# hd-gs.net
KiCad netlist of a schematic drawn in EAGLE
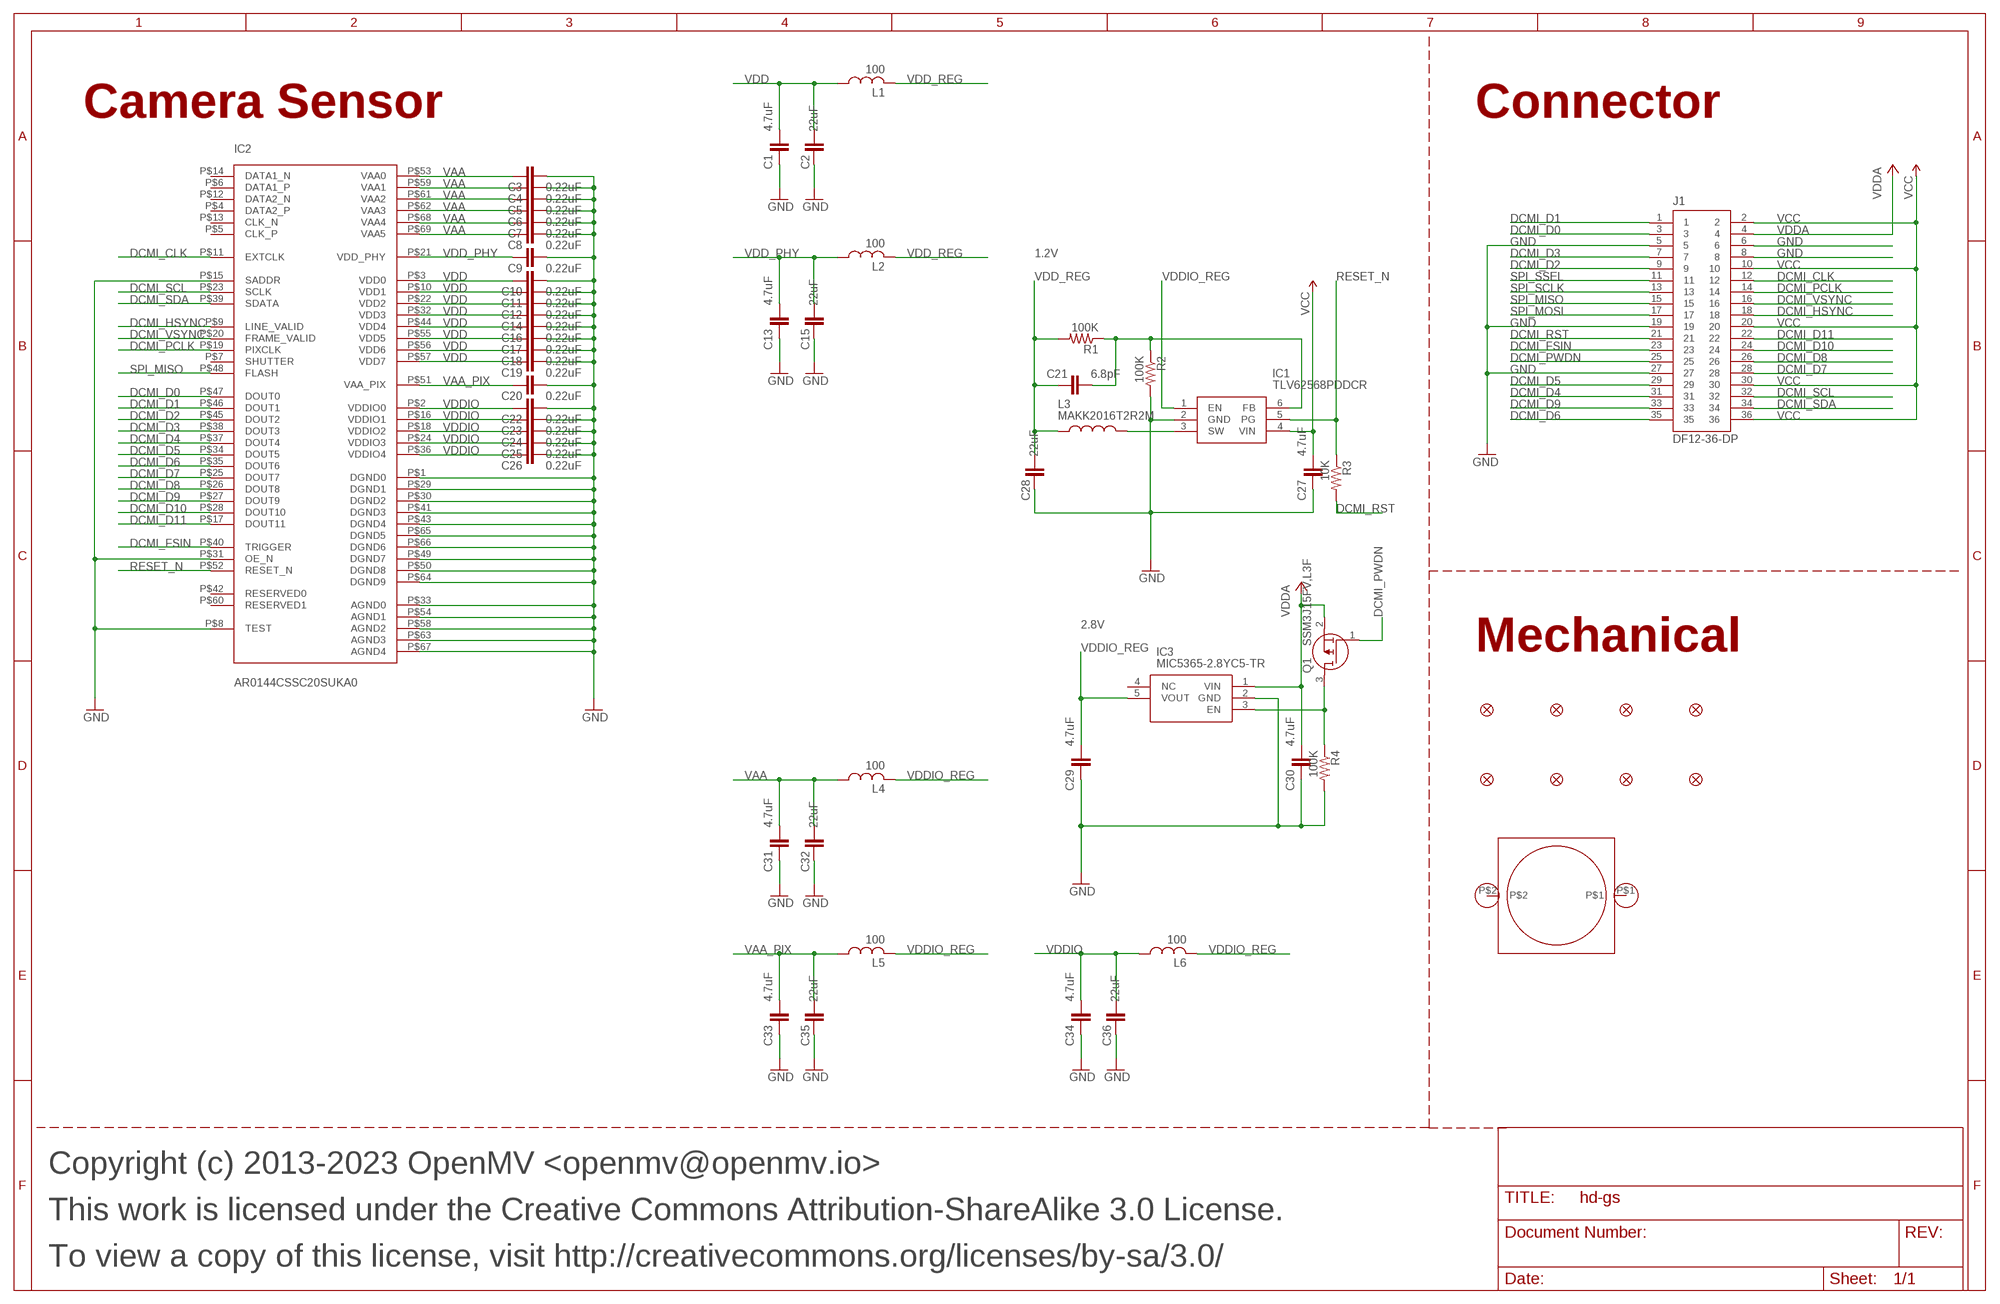
[diagram p0: schematic, sheet 1]

(export (version "E")
  (design (tool "Eeschema 10.0.6"))
  (components
    (comp (ref "C1")
      (value "4.7uF")
      (footprint "eagle-import:0402")
      (fields (field (name "MPN") "JMK105BBJ475MV-F"))
      (libsource (lib "eagle-import") (part "CAP_0402"))
    )
    (comp (ref "C2")
      (value "22uF")
      (footprint "eagle-import:0805")
      (fields (field (name "MPN") "CL21A226MQQNNNE"))
      (libsource (lib "eagle-import") (part "22UF-0805-6.3V-20%"))
    )
    (comp (ref "C3")
      (value "0.22uF")
      (footprint "eagle-import:C0201")
      (fields (field (name "MPN") "GRM033R60J224ME15D"))
      (libsource (lib "eagle-import") (part "C-EUC0201"))
    )
    (comp (ref "C4")
      (value "0.22uF")
      (footprint "eagle-import:C0201")
      (fields (field (name "MPN") "GRM033R60J224ME15D"))
      (libsource (lib "eagle-import") (part "C-EUC0201"))
    )
    (comp (ref "C5")
      (value "0.22uF")
      (footprint "eagle-import:C0201")
      (fields (field (name "MPN") "GRM033R60J224ME15D"))
      (libsource (lib "eagle-import") (part "C-EUC0201"))
    )
    (comp (ref "C6")
      (value "0.22uF")
      (footprint "eagle-import:C0201")
      (fields (field (name "MPN") "GRM033R60J224ME15D"))
      (libsource (lib "eagle-import") (part "C-EUC0201"))
    )
    (comp (ref "C7")
      (value "0.22uF")
      (footprint "eagle-import:C0201")
      (fields (field (name "MPN") "GRM033R60J224ME15D"))
      (libsource (lib "eagle-import") (part "C-EUC0201"))
    )
    (comp (ref "C8")
      (value "0.22uF")
      (footprint "eagle-import:C0201")
      (fields (field (name "MPN") "GRM033R60J224ME15D"))
      (libsource (lib "eagle-import") (part "C-EUC0201"))
    )
    (comp (ref "C9")
      (value "0.22uF")
      (footprint "eagle-import:C0201")
      (fields (field (name "MPN") "GRM033R60J224ME15D"))
      (libsource (lib "eagle-import") (part "C-EUC0201"))
    )
    (comp (ref "C10")
      (value "0.22uF")
      (footprint "eagle-import:C0201")
      (fields (field (name "MPN") "GRM033R60J224ME15D"))
      (libsource (lib "eagle-import") (part "C-EUC0201"))
    )
    (comp (ref "C11")
      (value "0.22uF")
      (footprint "eagle-import:C0201")
      (fields (field (name "MPN") "GRM033R60J224ME15D"))
      (libsource (lib "eagle-import") (part "C-EUC0201"))
    )
    (comp (ref "C12")
      (value "0.22uF")
      (footprint "eagle-import:C0201")
      (fields (field (name "MPN") "GRM033R60J224ME15D"))
      (libsource (lib "eagle-import") (part "C-EUC0201"))
    )
    (comp (ref "C13")
      (value "4.7uF")
      (footprint "eagle-import:0402")
      (fields (field (name "MPN") "JMK105BBJ475MV-F"))
      (libsource (lib "eagle-import") (part "CAP_0402"))
    )
    (comp (ref "C14")
      (value "0.22uF")
      (footprint "eagle-import:C0201")
      (fields (field (name "MPN") "GRM033R60J224ME15D"))
      (libsource (lib "eagle-import") (part "C-EUC0201"))
    )
    (comp (ref "C15")
      (value "22uF")
      (footprint "eagle-import:0805")
      (fields (field (name "MPN") "CL21A226MQQNNNE"))
      (libsource (lib "eagle-import") (part "22UF-0805-6.3V-20%"))
    )
    (comp (ref "C16")
      (value "0.22uF")
      (footprint "eagle-import:C0201")
      (fields (field (name "MPN") "GRM033R60J224ME15D"))
      (libsource (lib "eagle-import") (part "C-EUC0201"))
    )
    (comp (ref "C17")
      (value "0.22uF")
      (footprint "eagle-import:C0201")
      (fields (field (name "MPN") "GRM033R60J224ME15D"))
      (libsource (lib "eagle-import") (part "C-EUC0201"))
    )
    (comp (ref "C18")
      (value "0.22uF")
      (footprint "eagle-import:C0201")
      (fields (field (name "MPN") "GRM033R60J224ME15D"))
      (libsource (lib "eagle-import") (part "C-EUC0201"))
    )
    (comp (ref "C19")
      (value "0.22uF")
      (footprint "eagle-import:C0201")
      (fields (field (name "MPN") "GRM033R60J224ME15D"))
      (libsource (lib "eagle-import") (part "C-EUC0201"))
    )
    (comp (ref "C20")
      (value "0.22uF")
      (footprint "eagle-import:C0201")
      (fields (field (name "MPN") "GRM033R60J224ME15D"))
      (libsource (lib "eagle-import") (part "C-EUC0201"))
    )
    (comp (ref "C21")
      (value "6.8pF")
      (footprint "eagle-import:0402")
      (fields (field (name "MPN") "GRM1555C1H6R8DA01D"))
      (libsource (lib "eagle-import") (part "CAP_0402"))
    )
    (comp (ref "C22")
      (value "0.22uF")
      (footprint "eagle-import:C0201")
      (fields (field (name "MPN") "GRM033R60J224ME15D"))
      (libsource (lib "eagle-import") (part "C-EUC0201"))
    )
    (comp (ref "C23")
      (value "0.22uF")
      (footprint "eagle-import:C0201")
      (fields (field (name "MPN") "GRM033R60J224ME15D"))
      (libsource (lib "eagle-import") (part "C-EUC0201"))
    )
    (comp (ref "C24")
      (value "0.22uF")
      (footprint "eagle-import:C0201")
      (fields (field (name "MPN") "GRM033R60J224ME15D"))
      (libsource (lib "eagle-import") (part "C-EUC0201"))
    )
    (comp (ref "C25")
      (value "0.22uF")
      (footprint "eagle-import:C0201")
      (fields (field (name "MPN") "GRM033R60J224ME15D"))
      (libsource (lib "eagle-import") (part "C-EUC0201"))
    )
    (comp (ref "C26")
      (value "0.22uF")
      (footprint "eagle-import:C0201")
      (fields (field (name "MPN") "GRM033R60J224ME15D"))
      (libsource (lib "eagle-import") (part "C-EUC0201"))
    )
    (comp (ref "C27")
      (value "4.7uF")
      (footprint "eagle-import:0402")
      (fields (field (name "MPN") "JMK105BBJ475MV-F"))
      (libsource (lib "eagle-import") (part "CAP_0402"))
    )
    (comp (ref "C28")
      (value "22uF")
      (footprint "eagle-import:0805")
      (fields (field (name "MPN") "CL21A226MQQNNNE"))
      (libsource (lib "eagle-import") (part "22UF-0805-6.3V-20%"))
    )
    (comp (ref "C29")
      (value "4.7uF")
      (footprint "eagle-import:0402")
      (fields (field (name "MPN") "JMK105BBJ475MV-F"))
      (libsource (lib "eagle-import") (part "CAP_0402"))
    )
    (comp (ref "C30")
      (value "4.7uF")
      (footprint "eagle-import:0402")
      (fields (field (name "MPN") "JMK105BBJ475MV-F"))
      (libsource (lib "eagle-import") (part "CAP_0402"))
    )
    (comp (ref "C31")
      (value "4.7uF")
      (footprint "eagle-import:0402")
      (fields (field (name "MPN") "JMK105BBJ475MV-F"))
      (libsource (lib "eagle-import") (part "CAP_0402"))
    )
    (comp (ref "C32")
      (value "22uF")
      (footprint "eagle-import:0805")
      (fields (field (name "MPN") "CL21A226MQQNNNE"))
      (libsource (lib "eagle-import") (part "22UF-0805-6.3V-20%"))
    )
    (comp (ref "C33")
      (value "4.7uF")
      (footprint "eagle-import:0402")
      (fields (field (name "MPN") "JMK105BBJ475MV-F"))
      (libsource (lib "eagle-import") (part "CAP_0402"))
    )
    (comp (ref "C34")
      (value "4.7uF")
      (footprint "eagle-import:0402")
      (fields (field (name "MPN") "JMK105BBJ475MV-F"))
      (libsource (lib "eagle-import") (part "CAP_0402"))
    )
    (comp (ref "C35")
      (value "22uF")
      (footprint "eagle-import:0805")
      (fields (field (name "MPN") "CL21A226MQQNNNE"))
      (libsource (lib "eagle-import") (part "22UF-0805-6.3V-20%"))
    )
    (comp (ref "C36")
      (value "22uF")
      (footprint "eagle-import:0805")
      (fields (field (name "MPN") "CL21A226MQQNNNE"))
      (libsource (lib "eagle-import") (part "22UF-0805-6.3V-20%"))
    )
    (comp (ref "FD1")
      (value "FIDUCIAL1X2")
      (footprint "eagle-import:FIDUCIAL-1X2")
      (libsource (lib "eagle-import") (part "FIDUCIAL1X2"))
    )
    (comp (ref "FD2")
      (value "FIDUCIAL1X2")
      (footprint "eagle-import:FIDUCIAL-1X2")
      (libsource (lib "eagle-import") (part "FIDUCIAL1X2"))
    )
    (comp (ref "FD3")
      (value "FIDUCIAL1X2")
      (footprint "eagle-import:FIDUCIAL-1X2")
      (libsource (lib "eagle-import") (part "FIDUCIAL1X2"))
    )
    (comp (ref "FD4")
      (value "FIDUCIAL1X2")
      (footprint "eagle-import:FIDUCIAL-1X2")
      (libsource (lib "eagle-import") (part "FIDUCIAL1X2"))
    )
    (comp (ref "FD5")
      (value "FIDUCIAL1X2")
      (footprint "eagle-import:FIDUCIAL-1X2")
      (libsource (lib "eagle-import") (part "FIDUCIAL1X2"))
    )
    (comp (ref "FD6")
      (value "FIDUCIAL1X2")
      (footprint "eagle-import:FIDUCIAL-1X2")
      (libsource (lib "eagle-import") (part "FIDUCIAL1X2"))
    )
    (comp (ref "FD7")
      (value "FIDUCIAL1X2")
      (footprint "eagle-import:FIDUCIAL-1X2")
      (libsource (lib "eagle-import") (part "FIDUCIAL1X2"))
    )
    (comp (ref "FD8")
      (value "FIDUCIAL1X2")
      (footprint "eagle-import:FIDUCIAL-1X2")
      (libsource (lib "eagle-import") (part "FIDUCIAL1X2"))
    )
    (comp (ref "H1")
      (value "LENSMOUNT20MM")
      (footprint "eagle-import:LENSMOUNT-20MM")
      (libsource (lib "eagle-import") (part "LENSMOUNT20MM"))
    )
    (comp (ref "IC1")
      (value "TLV62568PDDCR")
      (footprint "eagle-import:SOT95P280X110-6N")
      (fields (field (name "MOUSER_PART_NUMBER") "595-TLV62568PDDCR"))
      (libsource (lib "eagle-import") (part "TLV62568PDDCR"))
    )
    (comp (ref "IC2")
      (value "AR0144CSSC20SUKA0")
      (footprint "eagle-import:AR0144CSSC20SUKA0")
      (fields (field (name "MPN") "AR0144CSSC20SUKA0-CRBR"))
      (libsource (lib "eagle-import") (part "AR0144CSSC20SUKA0"))
    )
    (comp (ref "IC3")
      (value "MIC5365-2.8YC5-TR")
      (footprint "eagle-import:SOT65P210X110-5N")
      (fields (field (name "MOUSER_PART_NUMBER") "998-MIC5365-2.8YC5TR"))
      (libsource (lib "eagle-import") (part "MIC5365-2.8YC5-TR"))
    )
    (comp (ref "J1")
      (value "DF12-36-DP")
      (footprint "eagle-import:DF12-36-DP")
      (fields (field (name "MPN") "DF12NB(3.0)-36DP-0.5V(51)"))
      (libsource (lib "eagle-import") (part "DF12-36-DP"))
    )
    (comp (ref "L1")
      (value "100")
      (footprint "eagle-import:0402")
      (fields (field (name "MPN") "MFBM1V1005-101-R"))
      (libsource (lib "eagle-import") (part "INDUCTOR_0402"))
    )
    (comp (ref "L2")
      (value "100")
      (footprint "eagle-import:0402")
      (fields (field (name "MPN") "MFBM1V1005-101-R"))
      (libsource (lib "eagle-import") (part "INDUCTOR_0402"))
    )
    (comp (ref "L3")
      (value "MAKK2016T2R2M")
      (footprint "eagle-import:INDC2016X100N")
      (fields (field (name "MF") "Taiyo Yuden"))
      (libsource (lib "eagle-import") (part "MAKK2016T2R2M"))
    )
    (comp (ref "L4")
      (value "100")
      (footprint "eagle-import:0402")
      (fields (field (name "MPN") "MFBM1V1005-101-R"))
      (libsource (lib "eagle-import") (part "INDUCTOR_0402"))
    )
    (comp (ref "L5")
      (value "100")
      (footprint "eagle-import:0402")
      (fields (field (name "MPN") "MFBM1V1005-101-R"))
      (libsource (lib "eagle-import") (part "INDUCTOR_0402"))
    )
    (comp (ref "L6")
      (value "100")
      (footprint "eagle-import:0402")
      (fields (field (name "MPN") "MFBM1V1005-101-R"))
      (libsource (lib "eagle-import") (part "INDUCTOR_0402"))
    )
    (comp (ref "Q1")
      (value "SSM3J15FV,L3F")
      (footprint "eagle-import:SSM3J15FVL3F")
      (fields (field (name "MOUSER_PART_NUMBER") "757-SSM3J15FVL3F"))
      (libsource (lib "eagle-import") (part "SSM3J15FV,L3F"))
    )
    (comp (ref "R1")
      (value "100K")
      (footprint "eagle-import:R0402")
      (fields (field (name "MPN") "AC0402FR-07100KL"))
      (libsource (lib "eagle-import") (part "R-US_R0402"))
    )
    (comp (ref "R2")
      (value "100K")
      (footprint "eagle-import:R0402")
      (fields (field (name "MPN") "AC0402FR-07100KL"))
      (libsource (lib "eagle-import") (part "R-US_R0402"))
    )
    (comp (ref "R3")
      (value "10K")
      (footprint "eagle-import:R0402")
      (fields (field (name "MPN") "AC0402FR-1310KL"))
      (libsource (lib "eagle-import") (part "R-US_R0402"))
    )
    (comp (ref "R4")
      (value "100K")
      (footprint "eagle-import:R0402")
      (fields (field (name "MPN") "AC0402FR-07100KL"))
      (libsource (lib "eagle-import") (part "R-US_R0402"))
    )
  )
  (nets
    (net (code "1") (name "/DCMI_CLK") (class "Default")
      (node (ref "IC2") (pin "P$11") (pinfunction "EXTCLK_P$11") (pintype "input"))
      (node (ref "J1") (pin "12") (pinfunction "12_12") (pintype "bidirectional"))
    )
    (net (code "2") (name "/DCMI_D0") (class "Default")
      (node (ref "IC2") (pin "P$47") (pinfunction "DOUT0_P$47") (pintype "output"))
      (node (ref "J1") (pin "3") (pinfunction "3_3") (pintype "bidirectional"))
    )
    (net (code "3") (name "/DCMI_D1") (class "Default")
      (node (ref "IC2") (pin "P$46") (pinfunction "DOUT1_P$46") (pintype "output"))
      (node (ref "J1") (pin "1") (pinfunction "1_1") (pintype "bidirectional"))
    )
    (net (code "4") (name "/DCMI_D2") (class "Default")
      (node (ref "IC2") (pin "P$45") (pinfunction "DOUT2_P$45") (pintype "output"))
      (node (ref "J1") (pin "9") (pinfunction "9_9") (pintype "bidirectional"))
    )
    (net (code "5") (name "/DCMI_D3") (class "Default")
      (node (ref "IC2") (pin "P$38") (pinfunction "DOUT3_P$38") (pintype "output"))
      (node (ref "J1") (pin "7") (pinfunction "7_7") (pintype "bidirectional"))
    )
    (net (code "6") (name "/DCMI_D4") (class "Default")
      (node (ref "IC2") (pin "P$37") (pinfunction "DOUT4_P$37") (pintype "output"))
      (node (ref "J1") (pin "31") (pinfunction "31_31") (pintype "bidirectional"))
    )
    (net (code "7") (name "/DCMI_D5") (class "Default")
      (node (ref "IC2") (pin "P$34") (pinfunction "DOUT5_P$34") (pintype "output"))
      (node (ref "J1") (pin "29") (pinfunction "29_29") (pintype "bidirectional"))
    )
    (net (code "8") (name "/DCMI_D6") (class "Default")
      (node (ref "IC2") (pin "P$35") (pinfunction "DOUT6_P$35") (pintype "output"))
      (node (ref "J1") (pin "35") (pinfunction "35_35") (pintype "bidirectional"))
    )
    (net (code "9") (name "/DCMI_D7") (class "Default")
      (node (ref "IC2") (pin "P$25") (pinfunction "DOUT7_P$25") (pintype "output"))
      (node (ref "J1") (pin "28") (pinfunction "28_28") (pintype "bidirectional"))
    )
    (net (code "10") (name "/DCMI_D8") (class "Default")
      (node (ref "IC2") (pin "P$26") (pinfunction "DOUT8_P$26") (pintype "output"))
      (node (ref "J1") (pin "26") (pinfunction "26_26") (pintype "bidirectional"))
    )
    (net (code "11") (name "/DCMI_D9") (class "Default")
      (node (ref "IC2") (pin "P$27") (pinfunction "DOUT9_P$27") (pintype "output"))
      (node (ref "J1") (pin "33") (pinfunction "33_33") (pintype "bidirectional"))
    )
    (net (code "12") (name "/DCMI_D10") (class "Default")
      (node (ref "IC2") (pin "P$28") (pinfunction "DOUT10_P$28") (pintype "output"))
      (node (ref "J1") (pin "24") (pinfunction "24_24") (pintype "bidirectional"))
    )
    (net (code "13") (name "/DCMI_D11") (class "Default")
      (node (ref "IC2") (pin "P$17") (pinfunction "DOUT11_P$17") (pintype "output"))
      (node (ref "J1") (pin "22") (pinfunction "22_22") (pintype "bidirectional"))
    )
    (net (code "14") (name "/DCMI_FSIN") (class "Default")
      (node (ref "IC2") (pin "P$40") (pinfunction "TRIGGER_P$40") (pintype "input"))
      (node (ref "J1") (pin "23") (pinfunction "23_23") (pintype "bidirectional"))
    )
    (net (code "15") (name "/DCMI_HSYNC") (class "Default")
      (node (ref "IC2") (pin "P$9") (pinfunction "LINE_VALID_P$9") (pintype "output"))
      (node (ref "J1") (pin "18") (pinfunction "18_18") (pintype "bidirectional"))
    )
    (net (code "16") (name "/DCMI_PCLK") (class "Default")
      (node (ref "IC2") (pin "P$19") (pinfunction "PIXCLK_P$19") (pintype "output"))
      (node (ref "J1") (pin "14") (pinfunction "14_14") (pintype "bidirectional"))
    )
    (net (code "17") (name "/DCMI_PWDN") (class "Default")
      (node (ref "J1") (pin "25") (pinfunction "25_25") (pintype "bidirectional"))
      (node (ref "Q1") (pin "1") (pinfunction "G_1") (pintype "bidirectional"))
    )
    (net (code "18") (name "/DCMI_RST") (class "Default")
      (node (ref "J1") (pin "21") (pinfunction "21_21") (pintype "bidirectional"))
      (node (ref "R3") (pin "2") (pinfunction "2_2") (pintype "passive"))
    )
    (net (code "19") (name "/DCMI_SCL") (class "Default")
      (node (ref "IC2") (pin "P$23") (pinfunction "SCLK_P$23") (pintype "input"))
      (node (ref "J1") (pin "32") (pinfunction "32_32") (pintype "bidirectional"))
    )
    (net (code "20") (name "/DCMI_SDA") (class "Default")
      (node (ref "IC2") (pin "P$39") (pinfunction "SDATA_P$39") (pintype "bidirectional"))
      (node (ref "J1") (pin "34") (pinfunction "34_34") (pintype "bidirectional"))
    )
    (net (code "21") (name "/DCMI_VSYNC") (class "Default")
      (node (ref "IC2") (pin "P$20") (pinfunction "FRAME_VALID_P$20") (pintype "output"))
      (node (ref "J1") (pin "16") (pinfunction "16_16") (pintype "bidirectional"))
    )
    (net (code "22") (name "/P$1") (class "Default")
      (node (ref "H1") (pin "P$1") (pinfunction "P$1_P$1") (pintype "power_in"))
    )
    (net (code "23") (name "/P$2") (class "Default")
      (node (ref "H1") (pin "P$2") (pinfunction "P$2_P$2") (pintype "power_in"))
    )
    (net (code "24") (name "/RESET_N") (class "Default")
      (node (ref "IC1") (pin "5") (pinfunction "PG_5") (pintype "bidirectional"))
      (node (ref "IC2") (pin "P$52") (pinfunction "RESET_N_P$52") (pintype "input"))
      (node (ref "R3") (pin "1") (pinfunction "1_1") (pintype "passive"))
    )
    (net (code "25") (name "/SPI_MISO") (class "Default")
      (node (ref "IC2") (pin "P$48") (pinfunction "FLASH_P$48") (pintype "output"))
      (node (ref "J1") (pin "15") (pinfunction "15_15") (pintype "bidirectional"))
    )
    (net (code "26") (name "/SPI_MOSI") (class "Default")
      (node (ref "J1") (pin "17") (pinfunction "17_17") (pintype "bidirectional"))
    )
    (net (code "27") (name "/SPI_SCLK") (class "Default")
      (node (ref "J1") (pin "13") (pinfunction "13_13") (pintype "bidirectional"))
    )
    (net (code "28") (name "/SPI_SSEL") (class "Default")
      (node (ref "J1") (pin "11") (pinfunction "11_11") (pintype "bidirectional"))
    )
    (net (code "29") (name "/VAA") (class "Default")
      (node (ref "C3") (pin "1") (pinfunction "1_1") (pintype "passive"))
      (node (ref "C31") (pin "2") (pinfunction "2_2") (pintype "passive"))
      (node (ref "C32") (pin "2") (pinfunction "2_2") (pintype "passive"))
      (node (ref "C4") (pin "1") (pinfunction "1_1") (pintype "passive"))
      (node (ref "C5") (pin "1") (pinfunction "1_1") (pintype "passive"))
      (node (ref "C6") (pin "1") (pinfunction "1_1") (pintype "passive"))
      (node (ref "C7") (pin "1") (pinfunction "1_1") (pintype "passive"))
      (node (ref "C8") (pin "1") (pinfunction "1_1") (pintype "passive"))
      (node (ref "IC2") (pin "P$53") (pinfunction "VAA0_P$53") (pintype "power_in"))
      (node (ref "IC2") (pin "P$59") (pinfunction "VAA1_P$59") (pintype "power_in"))
      (node (ref "IC2") (pin "P$61") (pinfunction "VAA2_P$61") (pintype "power_in"))
      (node (ref "IC2") (pin "P$62") (pinfunction "VAA3_P$62") (pintype "power_in"))
      (node (ref "IC2") (pin "P$68") (pinfunction "VAA4_P$68") (pintype "power_in"))
      (node (ref "IC2") (pin "P$69") (pinfunction "VAA5_P$69") (pintype "power_in"))
      (node (ref "L4") (pin "1") (pinfunction "P$1_1") (pintype "passive"))
    )
    (net (code "30") (name "/VAA_PIX") (class "Default")
      (node (ref "C20") (pin "1") (pinfunction "1_1") (pintype "passive"))
      (node (ref "C33") (pin "2") (pinfunction "2_2") (pintype "passive"))
      (node (ref "C35") (pin "2") (pinfunction "2_2") (pintype "passive"))
      (node (ref "IC2") (pin "P$51") (pinfunction "VAA_PIX_P$51") (pintype "power_in"))
      (node (ref "L5") (pin "1") (pinfunction "P$1_1") (pintype "passive"))
    )
    (net (code "31") (name "/VDD") (class "Default")
      (node (ref "C1") (pin "2") (pinfunction "2_2") (pintype "passive"))
      (node (ref "C10") (pin "1") (pinfunction "1_1") (pintype "passive"))
      (node (ref "C11") (pin "1") (pinfunction "1_1") (pintype "passive"))
      (node (ref "C12") (pin "1") (pinfunction "1_1") (pintype "passive"))
      (node (ref "C14") (pin "1") (pinfunction "1_1") (pintype "passive"))
      (node (ref "C16") (pin "1") (pinfunction "1_1") (pintype "passive"))
      (node (ref "C17") (pin "1") (pinfunction "1_1") (pintype "passive"))
      (node (ref "C18") (pin "1") (pinfunction "1_1") (pintype "passive"))
      (node (ref "C19") (pin "1") (pinfunction "1_1") (pintype "passive"))
      (node (ref "C2") (pin "2") (pinfunction "2_2") (pintype "passive"))
      (node (ref "IC2") (pin "P$10") (pinfunction "VDD1_P$10") (pintype "power_in"))
      (node (ref "IC2") (pin "P$22") (pinfunction "VDD2_P$22") (pintype "power_in"))
      (node (ref "IC2") (pin "P$3") (pinfunction "VDD0_P$3") (pintype "power_in"))
      (node (ref "IC2") (pin "P$32") (pinfunction "VDD3_P$32") (pintype "power_in"))
      (node (ref "IC2") (pin "P$44") (pinfunction "VDD4_P$44") (pintype "power_in"))
      (node (ref "IC2") (pin "P$55") (pinfunction "VDD5_P$55") (pintype "power_in"))
      (node (ref "IC2") (pin "P$56") (pinfunction "VDD6_P$56") (pintype "power_in"))
      (node (ref "IC2") (pin "P$57") (pinfunction "VDD7_P$57") (pintype "power_in"))
      (node (ref "L1") (pin "1") (pinfunction "P$1_1") (pintype "passive"))
    )
    (net (code "32") (name "/VDDIO") (class "Default")
      (node (ref "C22") (pin "1") (pinfunction "1_1") (pintype "passive"))
      (node (ref "C23") (pin "1") (pinfunction "1_1") (pintype "passive"))
      (node (ref "C24") (pin "1") (pinfunction "1_1") (pintype "passive"))
      (node (ref "C25") (pin "1") (pinfunction "1_1") (pintype "passive"))
      (node (ref "C26") (pin "1") (pinfunction "1_1") (pintype "passive"))
      (node (ref "C34") (pin "2") (pinfunction "2_2") (pintype "passive"))
      (node (ref "C36") (pin "2") (pinfunction "2_2") (pintype "passive"))
      (node (ref "IC2") (pin "P$16") (pinfunction "VDDIO1_P$16") (pintype "power_in"))
      (node (ref "IC2") (pin "P$18") (pinfunction "VDDIO2_P$18") (pintype "power_in"))
      (node (ref "IC2") (pin "P$2") (pinfunction "VDDIO0_P$2") (pintype "power_in"))
      (node (ref "IC2") (pin "P$24") (pinfunction "VDDIO3_P$24") (pintype "power_in"))
      (node (ref "IC2") (pin "P$36") (pinfunction "VDDIO4_P$36") (pintype "power_in"))
      (node (ref "L6") (pin "1") (pinfunction "P$1_1") (pintype "passive"))
    )
    (net (code "33") (name "/VDDIO_REG") (class "Default")
      (node (ref "C29") (pin "2") (pinfunction "2_2") (pintype "passive"))
      (node (ref "IC1") (pin "1") (pinfunction "EN_1") (pintype "bidirectional"))
      (node (ref "IC3") (pin "5") (pinfunction "VOUT_5") (pintype "bidirectional"))
      (node (ref "L4") (pin "2") (pinfunction "P$2_2") (pintype "passive"))
      (node (ref "L5") (pin "2") (pinfunction "P$2_2") (pintype "passive"))
      (node (ref "L6") (pin "2") (pinfunction "P$2_2") (pintype "passive"))
    )
    (net (code "34") (name "/VDD_PHY") (class "Default")
      (node (ref "C13") (pin "2") (pinfunction "2_2") (pintype "passive"))
      (node (ref "C15") (pin "2") (pinfunction "2_2") (pintype "passive"))
      (node (ref "C9") (pin "1") (pinfunction "1_1") (pintype "passive"))
      (node (ref "IC2") (pin "P$21") (pinfunction "VDD_PHY_P$21") (pintype "power_in"))
      (node (ref "L2") (pin "1") (pinfunction "P$1_1") (pintype "passive"))
    )
    (net (code "35") (name "/VDD_REG") (class "Default")
      (node (ref "C21") (pin "1") (pinfunction "1_1") (pintype "passive"))
      (node (ref "C28") (pin "2") (pinfunction "2_2") (pintype "passive"))
      (node (ref "L1") (pin "2") (pinfunction "P$2_2") (pintype "passive"))
      (node (ref "L2") (pin "2") (pinfunction "P$2_2") (pintype "passive"))
      (node (ref "L3") (pin "1") (pinfunction "1_1") (pintype "passive"))
      (node (ref "R1") (pin "2") (pinfunction "2_2") (pintype "passive"))
    )
    (net (code "36") (name "GND") (class "Default")
      (node (ref "C1") (pin "1") (pinfunction "1_1") (pintype "passive"))
      (node (ref "C10") (pin "2") (pinfunction "2_2") (pintype "passive"))
      (node (ref "C11") (pin "2") (pinfunction "2_2") (pintype "passive"))
      (node (ref "C12") (pin "2") (pinfunction "2_2") (pintype "passive"))
      (node (ref "C13") (pin "1") (pinfunction "1_1") (pintype "passive"))
      (node (ref "C14") (pin "2") (pinfunction "2_2") (pintype "passive"))
      (node (ref "C15") (pin "1") (pinfunction "1_1") (pintype "passive"))
      (node (ref "C16") (pin "2") (pinfunction "2_2") (pintype "passive"))
      (node (ref "C17") (pin "2") (pinfunction "2_2") (pintype "passive"))
      (node (ref "C18") (pin "2") (pinfunction "2_2") (pintype "passive"))
      (node (ref "C19") (pin "2") (pinfunction "2_2") (pintype "passive"))
      (node (ref "C2") (pin "1") (pinfunction "1_1") (pintype "passive"))
      (node (ref "C20") (pin "2") (pinfunction "2_2") (pintype "passive"))
      (node (ref "C22") (pin "2") (pinfunction "2_2") (pintype "passive"))
      (node (ref "C23") (pin "2") (pinfunction "2_2") (pintype "passive"))
      (node (ref "C24") (pin "2") (pinfunction "2_2") (pintype "passive"))
      (node (ref "C25") (pin "2") (pinfunction "2_2") (pintype "passive"))
      (node (ref "C26") (pin "2") (pinfunction "2_2") (pintype "passive"))
      (node (ref "C27") (pin "1") (pinfunction "1_1") (pintype "passive"))
      (node (ref "C28") (pin "1") (pinfunction "1_1") (pintype "passive"))
      (node (ref "C29") (pin "1") (pinfunction "1_1") (pintype "passive"))
      (node (ref "C3") (pin "2") (pinfunction "2_2") (pintype "passive"))
      (node (ref "C30") (pin "1") (pinfunction "1_1") (pintype "passive"))
      (node (ref "C31") (pin "1") (pinfunction "1_1") (pintype "passive"))
      (node (ref "C32") (pin "1") (pinfunction "1_1") (pintype "passive"))
      (node (ref "C33") (pin "1") (pinfunction "1_1") (pintype "passive"))
      (node (ref "C34") (pin "1") (pinfunction "1_1") (pintype "passive"))
      (node (ref "C35") (pin "1") (pinfunction "1_1") (pintype "passive"))
      (node (ref "C36") (pin "1") (pinfunction "1_1") (pintype "passive"))
      (node (ref "C4") (pin "2") (pinfunction "2_2") (pintype "passive"))
      (node (ref "C5") (pin "2") (pinfunction "2_2") (pintype "passive"))
      (node (ref "C6") (pin "2") (pinfunction "2_2") (pintype "passive"))
      (node (ref "C7") (pin "2") (pinfunction "2_2") (pintype "passive"))
      (node (ref "C8") (pin "2") (pinfunction "2_2") (pintype "passive"))
      (node (ref "C9") (pin "2") (pinfunction "2_2") (pintype "passive"))
      (node (ref "IC1") (pin "2") (pinfunction "GND_2") (pintype "bidirectional"))
      (node (ref "IC2") (pin "P$1") (pinfunction "DGND0_P$1") (pintype "power_in"))
      (node (ref "IC2") (pin "P$15") (pinfunction "SADDR_P$15") (pintype "input"))
      (node (ref "IC2") (pin "P$29") (pinfunction "DGND1_P$29") (pintype "power_in"))
      (node (ref "IC2") (pin "P$30") (pinfunction "DGND2_P$30") (pintype "power_in"))
      (node (ref "IC2") (pin "P$31") (pinfunction "OE_N_P$31") (pintype "input"))
      (node (ref "IC2") (pin "P$33") (pinfunction "AGND0_P$33") (pintype "power_in"))
      (node (ref "IC2") (pin "P$41") (pinfunction "DGND3_P$41") (pintype "power_in"))
      (node (ref "IC2") (pin "P$43") (pinfunction "DGND4_P$43") (pintype "power_in"))
      (node (ref "IC2") (pin "P$49") (pinfunction "DGND7_P$49") (pintype "power_in"))
      (node (ref "IC2") (pin "P$50") (pinfunction "DGND8_P$50") (pintype "power_in"))
      (node (ref "IC2") (pin "P$54") (pinfunction "AGND1_P$54") (pintype "power_in"))
      (node (ref "IC2") (pin "P$58") (pinfunction "AGND2_P$58") (pintype "power_in"))
      (node (ref "IC2") (pin "P$63") (pinfunction "AGND3_P$63") (pintype "power_in"))
      (node (ref "IC2") (pin "P$64") (pinfunction "DGND9_P$64") (pintype "power_in"))
      (node (ref "IC2") (pin "P$65") (pinfunction "DGND5_P$65") (pintype "power_in"))
      (node (ref "IC2") (pin "P$66") (pinfunction "DGND6_P$66") (pintype "power_in"))
      (node (ref "IC2") (pin "P$67") (pinfunction "AGND4_P$67") (pintype "power_in"))
      (node (ref "IC2") (pin "P$8") (pinfunction "TEST_P$8") (pintype "input"))
      (node (ref "IC3") (pin "2") (pinfunction "GND_2") (pintype "bidirectional"))
      (node (ref "J1") (pin "19") (pinfunction "19_19") (pintype "bidirectional"))
      (node (ref "J1") (pin "27") (pinfunction "27_27") (pintype "bidirectional"))
      (node (ref "J1") (pin "5") (pinfunction "5_5") (pintype "bidirectional"))
      (node (ref "J1") (pin "6") (pinfunction "6_6") (pintype "bidirectional"))
      (node (ref "J1") (pin "8") (pinfunction "8_8") (pintype "bidirectional"))
      (node (ref "R2") (pin "2") (pinfunction "2_2") (pintype "passive"))
      (node (ref "R4") (pin "2") (pinfunction "2_2") (pintype "passive"))
    )
    (net (code "37") (name "Net-(IC1-FB)") (class "Default")
      (node (ref "C21") (pin "2") (pinfunction "2_2") (pintype "passive"))
      (node (ref "IC1") (pin "6") (pinfunction "FB_6") (pintype "bidirectional"))
      (node (ref "R1") (pin "1") (pinfunction "1_1") (pintype "passive"))
      (node (ref "R2") (pin "1") (pinfunction "1_1") (pintype "passive"))
    )
    (net (code "38") (name "Net-(IC1-SW)") (class "Default")
      (node (ref "IC1") (pin "3") (pinfunction "SW_3") (pintype "bidirectional"))
      (node (ref "L3") (pin "2") (pinfunction "2_2") (pintype "passive"))
    )
    (net (code "39") (name "Net-(IC3-EN)") (class "Default")
      (node (ref "IC3") (pin "3") (pinfunction "EN_3") (pintype "bidirectional"))
      (node (ref "Q1") (pin "3") (pinfunction "D_3") (pintype "bidirectional"))
      (node (ref "R4") (pin "1") (pinfunction "1_1") (pintype "passive"))
    )
    (net (code "40") (name "VCC") (class "Default")
      (node (ref "C27") (pin "2") (pinfunction "2_2") (pintype "passive"))
      (node (ref "IC1") (pin "4") (pinfunction "VIN_4") (pintype "bidirectional"))
      (node (ref "J1") (pin "10") (pinfunction "10_10") (pintype "bidirectional"))
      (node (ref "J1") (pin "2") (pinfunction "2_2") (pintype "bidirectional"))
      (node (ref "J1") (pin "20") (pinfunction "20_20") (pintype "bidirectional"))
      (node (ref "J1") (pin "30") (pinfunction "30_30") (pintype "bidirectional"))
      (node (ref "J1") (pin "36") (pinfunction "36_36") (pintype "bidirectional"))
    )
    (net (code "41") (name "VDDA") (class "Default")
      (node (ref "C30") (pin "2") (pinfunction "2_2") (pintype "passive"))
      (node (ref "IC3") (pin "1") (pinfunction "VIN_1") (pintype "bidirectional"))
      (node (ref "J1") (pin "4") (pinfunction "4_4") (pintype "bidirectional"))
      (node (ref "Q1") (pin "2") (pinfunction "S_2") (pintype "bidirectional"))
    )
    (net (code "42") (name "unconnected-(IC2-CLK_N-PadP$13)") (class "Default")
      (node (ref "IC2") (pin "P$13") (pinfunction "CLK_N_P$13") (pintype "output"))
    )
    (net (code "43") (name "unconnected-(IC2-CLK_P-PadP$5)") (class "Default")
      (node (ref "IC2") (pin "P$5") (pinfunction "CLK_P_P$5") (pintype "output"))
    )
    (net (code "44") (name "unconnected-(IC2-DATA1_N-PadP$14)") (class "Default")
      (node (ref "IC2") (pin "P$14") (pinfunction "DATA1_N_P$14") (pintype "output"))
    )
    (net (code "45") (name "unconnected-(IC2-DATA1_P-PadP$6)") (class "Default")
      (node (ref "IC2") (pin "P$6") (pinfunction "DATA1_P_P$6") (pintype "output"))
    )
    (net (code "46") (name "unconnected-(IC2-DATA2_N-PadP$12)") (class "Default")
      (node (ref "IC2") (pin "P$12") (pinfunction "DATA2_N_P$12") (pintype "output"))
    )
    (net (code "47") (name "unconnected-(IC2-DATA2_P-PadP$4)") (class "Default")
      (node (ref "IC2") (pin "P$4") (pinfunction "DATA2_P_P$4") (pintype "output"))
    )
    (net (code "48") (name "unconnected-(IC2-RESERVED0-PadP$42)") (class "Default")
      (node (ref "IC2") (pin "P$42") (pinfunction "RESERVED0_P$42") (pintype "input"))
    )
    (net (code "49") (name "unconnected-(IC2-RESERVED1-PadP$60)") (class "Default")
      (node (ref "IC2") (pin "P$60") (pinfunction "RESERVED1_P$60") (pintype "input"))
    )
    (net (code "50") (name "unconnected-(IC2-SHUTTER-PadP$7)") (class "Default")
      (node (ref "IC2") (pin "P$7") (pinfunction "SHUTTER_P$7") (pintype "output"))
    )
    (net (code "51") (name "unconnected-(IC3-NC-Pad4)") (class "Default")
      (node (ref "IC3") (pin "4") (pinfunction "NC_4") (pintype "no_connect"))
    )
  )
)
